# Abhinav_Schematic_May_15_2025.net
KiCad netlist of a schematic drawn in EasyEDA
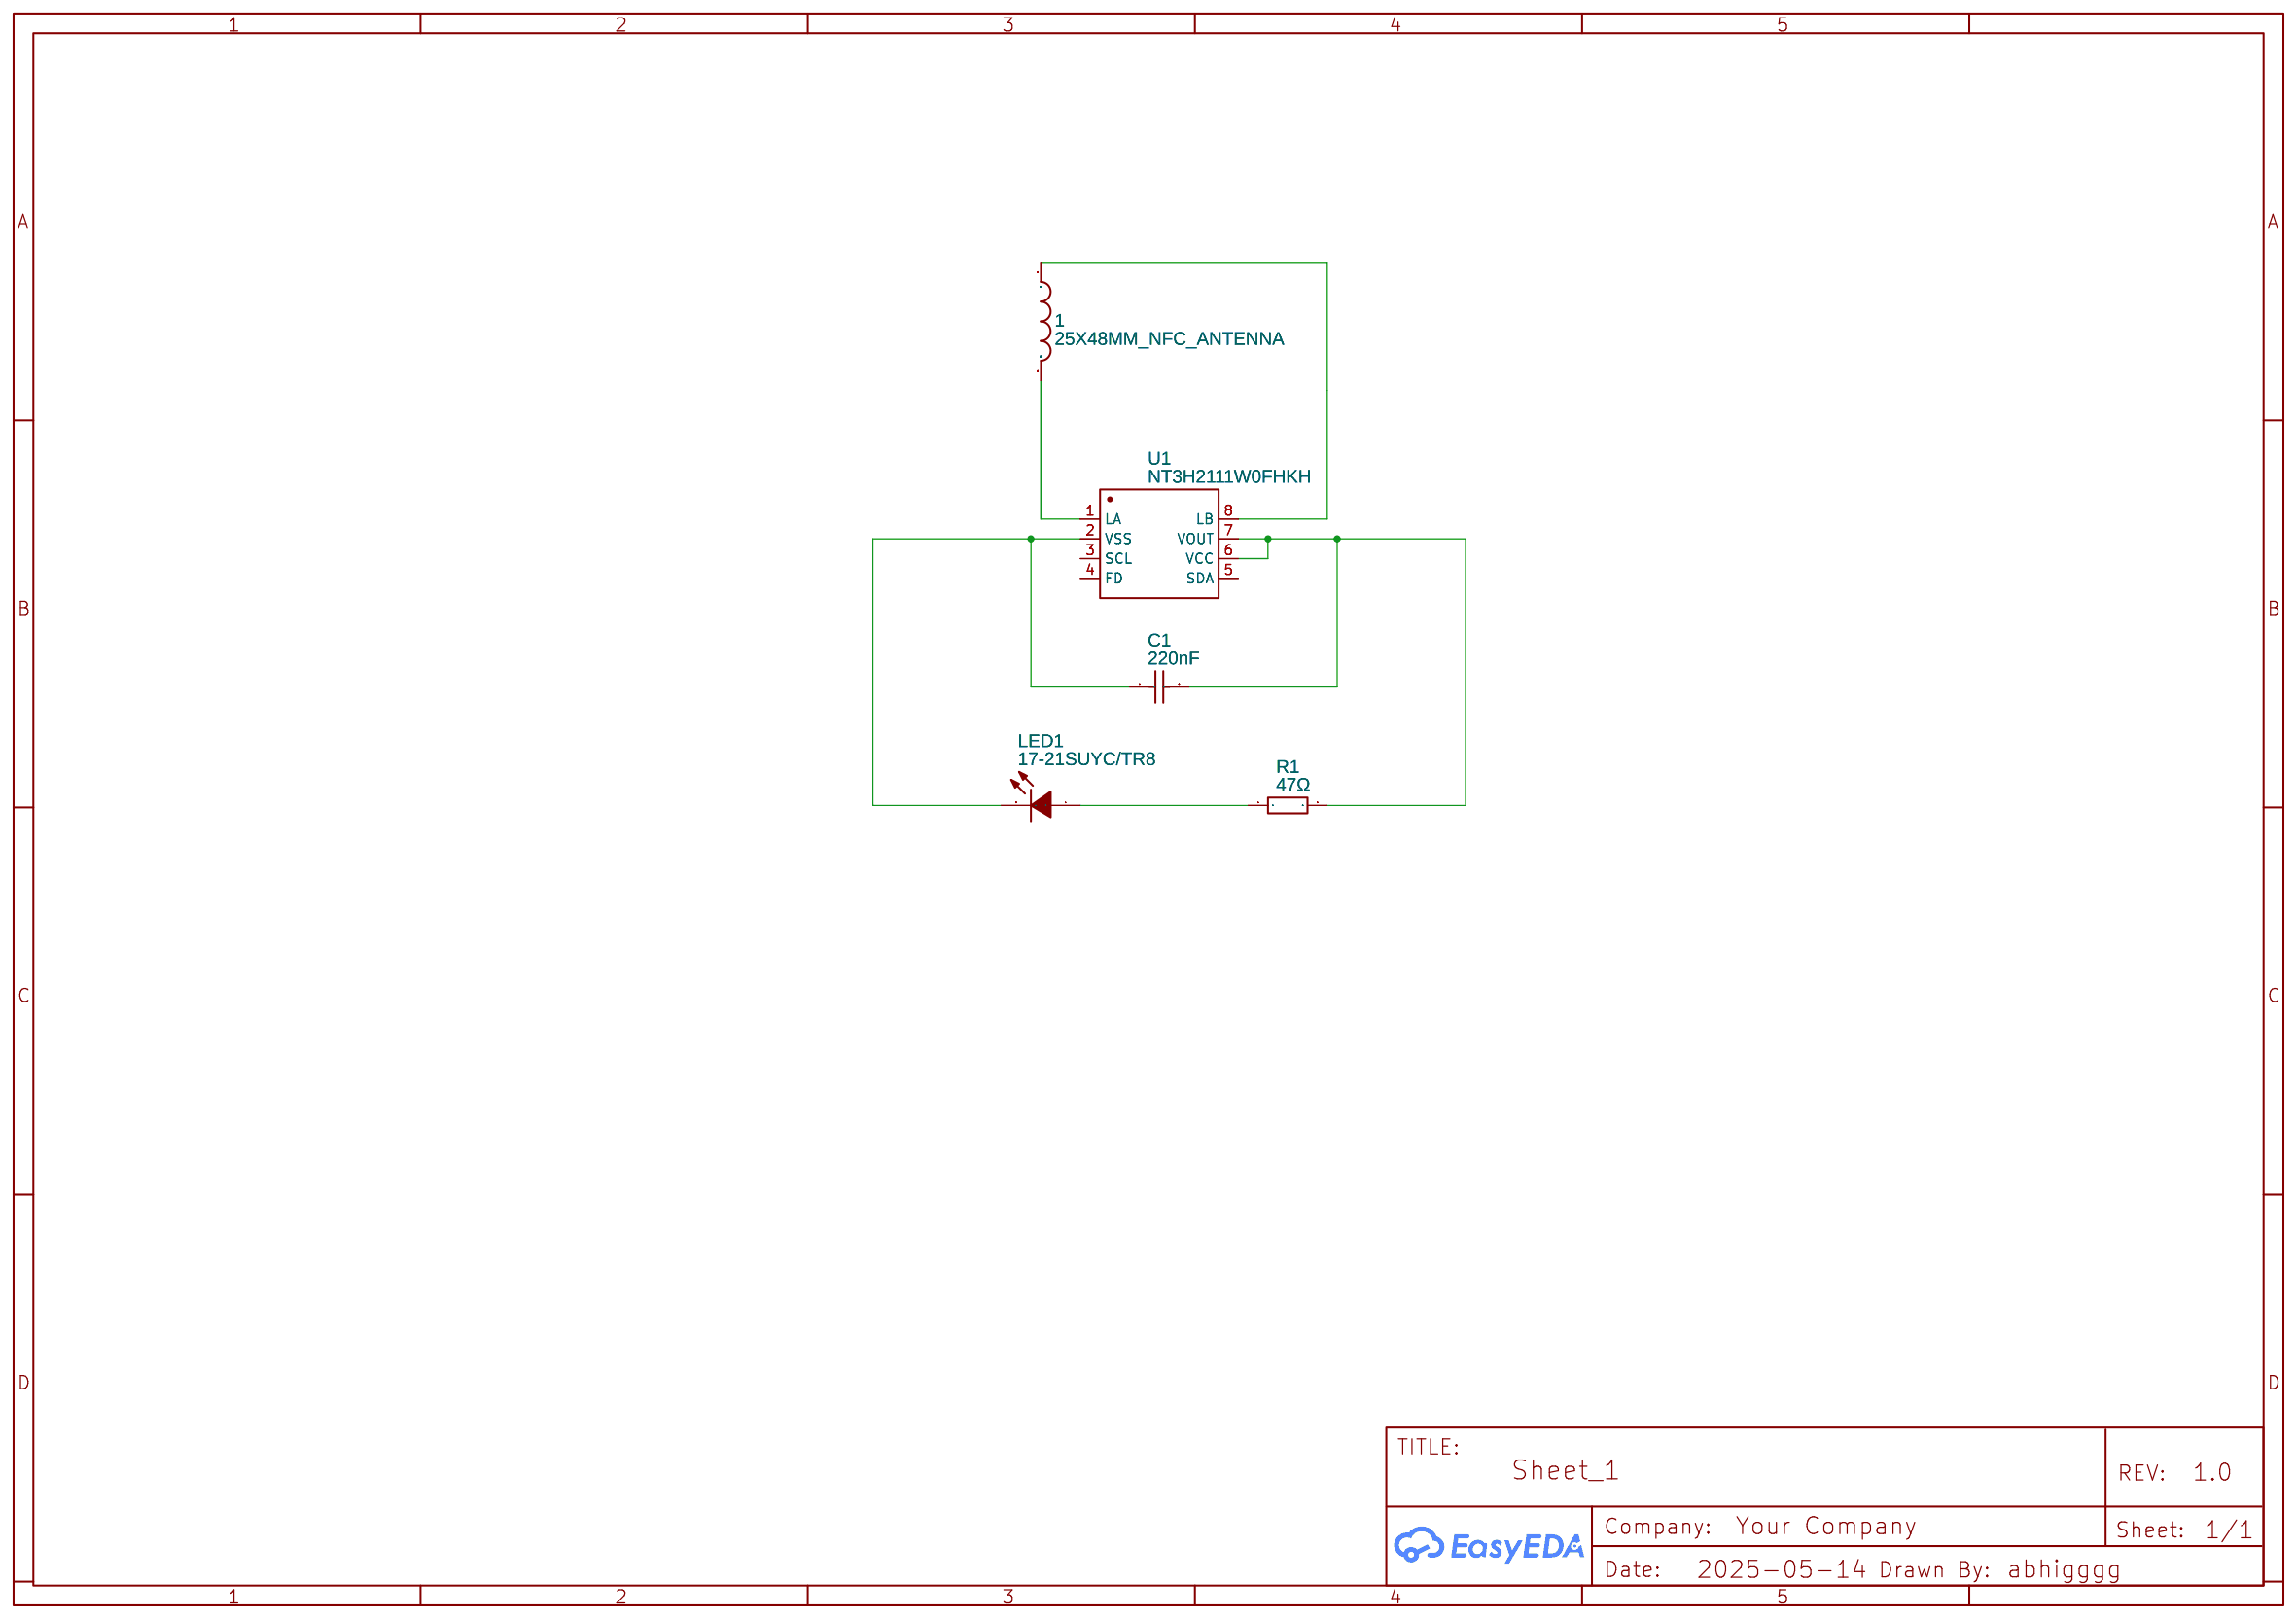
[diagram p0: schematic sheet]

(export (version "E")
  (design (tool "Eeschema 10.0.6"))
  (components
    (comp (ref "1") (value "25X48MM_NFC_ANTENNA") (libsource (lib "") (part "25X48MM_NFC_ANTENNA")))
    (comp (ref "C1")
      (value "220nF")
      (fields
        (field (name "Manufacturer Part") "CL10B224KA8NNNC")
        (field (name "Manufacturer") "SAMSUNG(三星)")
      )
      (libsource (lib "") (part "CL10B224KA8NNNC"))
    )
    (comp (ref "LED1")
      (value "17-21SUYC/TR8")
      (fields (field (name "Manufacturer Part") "KT-0805黄灯") (field (name "Manufacturer") "KENTO"))
      (libsource (lib "") (part "17-21SUYC/TR8"))
    )
    (comp (ref "R1")
      (value "47Ω")
      (fields
        (field (name "Manufacturer Part") "0603WAF470JT5E")
        (field (name "Manufacturer") "UNI-ROYAL(厚声)")
      )
      (libsource (lib "") (part "0603WAF470JT5E"))
    )
    (comp (ref "U1")
      (value "NT3H2111W0FHKH")
      (fields (field (name "Manufacturer") "NXP(恩智浦)"))
      (libsource (lib "") (part "NT3H2111W0FHKH"))
    )
  )
  (nets
    (net (code "1") (name "Net-(LED1-+)") (class "Default")
      (node (ref "LED1") (pin "1") (pinfunction "+_1") (pintype "unspecified"))
      (node (ref "R1") (pin "1") (pinfunction "1_1") (pintype "input"))
    )
    (net (code "2") (name "Net-(LED1--)") (class "Default")
      (node (ref "C1") (pin "1") (pinfunction "1_1") (pintype "input"))
      (node (ref "LED1") (pin "2") (pinfunction "-_2") (pintype "unspecified"))
      (node (ref "U1") (pin "2") (pinfunction "VSS_2") (pintype "unspecified"))
    )
    (net (code "3") (name "Net-(U1-LA)") (class "Default")
      (node (ref "1") (pin "P$2") (pinfunction "P$2_P$2") (pintype "bidirectional"))
      (node (ref "U1") (pin "1") (pinfunction "LA_1") (pintype "unspecified"))
    )
    (net (code "4") (name "Net-(U1-LB)") (class "Default")
      (node (ref "1") (pin "P$1") (pinfunction "P$1_P$1") (pintype "bidirectional"))
      (node (ref "U1") (pin "8") (pinfunction "LB_8") (pintype "unspecified"))
    )
    (net (code "5") (name "Net-(U1-VCC)") (class "Default")
      (node (ref "C1") (pin "2") (pinfunction "2_2") (pintype "input"))
      (node (ref "R1") (pin "2") (pinfunction "2_2") (pintype "input"))
      (node (ref "U1") (pin "6") (pinfunction "VCC_6") (pintype "unspecified"))
      (node (ref "U1") (pin "7") (pinfunction "VOUT_7") (pintype "unspecified"))
    )
    (net (code "6") (name "unconnected-(U1-FD-Pad4)") (class "Default")
      (node (ref "U1") (pin "4") (pinfunction "FD_4") (pintype "unspecified"))
    )
    (net (code "7") (name "unconnected-(U1-SCL-Pad3)") (class "Default")
      (node (ref "U1") (pin "3") (pinfunction "SCL_3") (pintype "unspecified"))
    )
    (net (code "8") (name "unconnected-(U1-SDA-Pad5)") (class "Default")
      (node (ref "U1") (pin "5") (pinfunction "SDA_5") (pintype "unspecified"))
    )
  )
)
